# SparkFun_MicroMod_ESP32_27012021.net
KiCad netlist of a schematic drawn in EAGLE
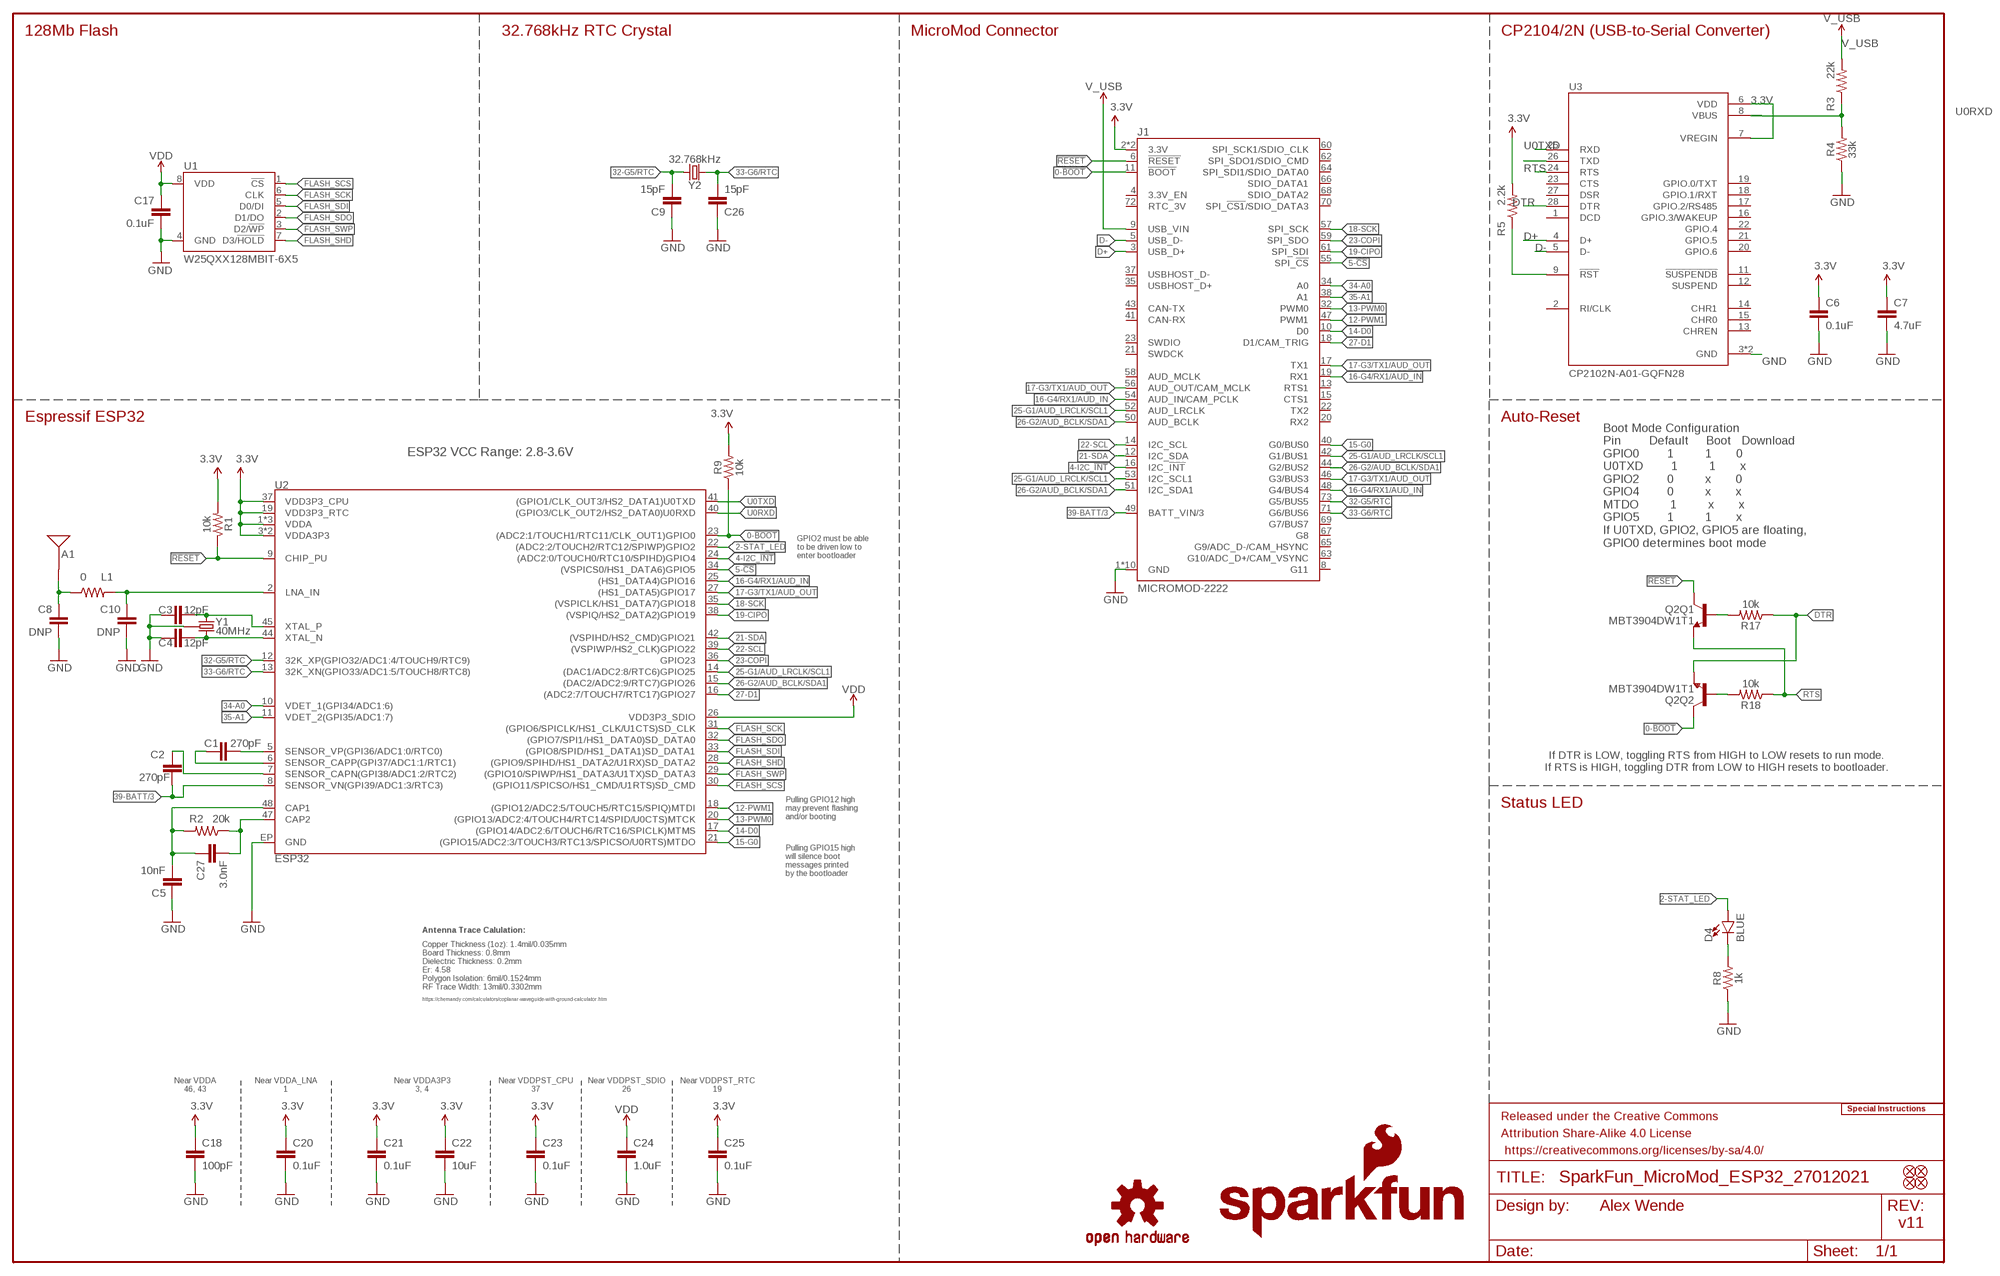
[diagram p0: schematic, sheet 1]

(export (version "E")
  (design (tool "Eeschema 10.0.6"))
  (components
    (comp (ref "A1")
      (value "ANTENNA2.4GHZ-8.0X1.0MM")
      (footprint "eagle-import:ANT-2.4GHZ-8.0X1.0MM")
      (libsource (lib "eagle-import") (part "ANTENNA2.4GHZ-8.0X1.0MM"))
    )
    (comp (ref "C1")
      (value "270pF")
      (footprint "eagle-import:0402-TIGHT")
      (libsource (lib "eagle-import") (part "270PF-0402T-50V-5%"))
    )
    (comp (ref "C2")
      (value "270pF")
      (footprint "eagle-import:0402-TIGHT")
      (libsource (lib "eagle-import") (part "270PF-0402T-50V-5%"))
    )
    (comp (ref "C3")
      (value "12pF")
      (footprint "eagle-import:0402-TIGHT")
      (libsource (lib "eagle-import") (part "12PF-0402T-50V-5%"))
    )
    (comp (ref "C4")
      (value "12pF")
      (footprint "eagle-import:0402-TIGHT")
      (libsource (lib "eagle-import") (part "12PF-0402T-50V-5%"))
    )
    (comp (ref "C5")
      (value "10nF")
      (footprint "eagle-import:0402-TIGHT")
      (libsource (lib "eagle-import") (part "10NF-0402T-25V-10%"))
    )
    (comp (ref "C6")
      (value "0.1uF")
      (footprint "eagle-import:0402-TIGHT")
      (libsource (lib "eagle-import") (part "0.1UF-0402T-16V-10%"))
    )
    (comp (ref "C7")
      (value "4.7uF")
      (footprint "eagle-import:0402-TIGHT")
      (libsource (lib "eagle-import") (part "4.7UF-0402_TIGHT-6.3V-20%-X5R"))
    )
    (comp (ref "C8")
      (value "DNP")
      (footprint "eagle-import:0402-TIGHT")
      (libsource (lib "eagle-import") (part "CAP-0402-TIGHT"))
    )
    (comp (ref "C9")
      (value "15pF")
      (footprint "eagle-import:0402-TIGHT")
      (libsource (lib "eagle-import") (part "15PF-0402T-50V-5%"))
    )
    (comp (ref "C10")
      (value "DNP")
      (footprint "eagle-import:0402-TIGHT")
      (libsource (lib "eagle-import") (part "CAP-0402-TIGHT"))
    )
    (comp (ref "C17")
      (value "0.1uF")
      (footprint "eagle-import:0402-TIGHT")
      (libsource (lib "eagle-import") (part "0.1UF-0402T-16V-10%"))
    )
    (comp (ref "C18")
      (value "100pF")
      (footprint "eagle-import:0402-TIGHT")
      (libsource (lib "eagle-import") (part "100PF-0402T-50V-5%"))
    )
    (comp (ref "C20")
      (value "0.1uF")
      (footprint "eagle-import:0402-TIGHT")
      (libsource (lib "eagle-import") (part "0.1UF-0402T-16V-10%"))
    )
    (comp (ref "C21")
      (value "0.1uF")
      (footprint "eagle-import:0402-TIGHT")
      (libsource (lib "eagle-import") (part "0.1UF-0402T-16V-10%"))
    )
    (comp (ref "C22")
      (value "10uF")
      (footprint "eagle-import:0402-TIGHT")
      (libsource (lib "eagle-import") (part "10UF-0402T-6.3V-20%"))
    )
    (comp (ref "C23")
      (value "0.1uF")
      (footprint "eagle-import:0402-TIGHT")
      (libsource (lib "eagle-import") (part "0.1UF-0402T-16V-10%"))
    )
    (comp (ref "C24")
      (value "1.0uF")
      (footprint "eagle-import:0402-TIGHT")
      (libsource (lib "eagle-import") (part "1.0UF-0402T-16V-10%"))
    )
    (comp (ref "C25")
      (value "0.1uF")
      (footprint "eagle-import:0402-TIGHT")
      (libsource (lib "eagle-import") (part "0.1UF-0402T-16V-10%"))
    )
    (comp (ref "C26")
      (value "15pF")
      (footprint "eagle-import:0402-TIGHT")
      (libsource (lib "eagle-import") (part "15PF-0402T-50V-5%"))
    )
    (comp (ref "C27")
      (value "3.0nF")
      (footprint "eagle-import:0402-TIGHT")
      (libsource (lib "eagle-import") (part "3.0NF-0402T-50V-5%"))
    )
    (comp (ref "D4")
      (value "BLUE")
      (footprint "eagle-import:LED-0603")
      (libsource (lib "eagle-import") (part "LED-BLUE0603"))
    )
    (comp (ref "FD1")
      (value "FIDUCIALUFIDUCIAL")
      (footprint "eagle-import:FIDUCIAL-MICRO")
      (libsource (lib "eagle-import") (part "FIDUCIALUFIDUCIAL"))
    )
    (comp (ref "FD2")
      (value "FIDUCIALUFIDUCIAL")
      (footprint "eagle-import:FIDUCIAL-MICRO")
      (libsource (lib "eagle-import") (part "FIDUCIALUFIDUCIAL"))
    )
    (comp (ref "FD3")
      (value "FIDUCIALUFIDUCIAL")
      (footprint "eagle-import:FIDUCIAL-MICRO")
      (libsource (lib "eagle-import") (part "FIDUCIALUFIDUCIAL"))
    )
    (comp (ref "FD4")
      (value "FIDUCIALUFIDUCIAL")
      (footprint "eagle-import:FIDUCIAL-MICRO")
      (libsource (lib "eagle-import") (part "FIDUCIALUFIDUCIAL"))
    )
    (comp (ref "FRAME1")
      (value "FRAME-LEDGER")
      (footprint "eagle-import:CREATIVE_COMMONS")
      (libsource (lib "eagle-import") (part "FRAME-LEDGER"))
    )
    (comp (ref "J1")
      (value "MICROMOD-2222")
      (footprint "eagle-import:M.2-CARD-E-22")
      (libsource (lib "eagle-import") (part "MICROMOD-2222"))
    )
    (comp (ref "L1")
      (value "0")
      (footprint "eagle-import:0402-TIGHT")
      (libsource (lib "eagle-import") (part "0OHM-0402T-1/10W"))
    )
    (comp (ref "LOGO1")
      (value "SPECIAL_INSTRUCTIONS-ORDERING")
      (footprint "eagle-import:ORDERING_INSTRUCTIONS")
      (libsource (lib "eagle-import") (part "SPECIAL_INSTRUCTIONS-ORDERING"))
    )
    (comp (ref "LOGO2")
      (value "SFE_LOGO_NAME_FLAME.1_INCH")
      (footprint "eagle-import:SFE_LOGO_NAME_FLAME_.1")
      (libsource (lib "eagle-import") (part "SFE_LOGO_NAME_FLAME.1_INCH"))
    )
    (comp (ref "LOGO3")
      (value "OSHW-LOGOS")
      (footprint "eagle-import:OSHW-LOGO-S")
      (libsource (lib "eagle-import") (part "OSHW-LOGOS"))
    )
    (comp (ref "Q2")
      (value "MBT3904DW1T1")
      (footprint "eagle-import:SC70-6")
      (libsource (lib "eagle-import") (part "TRANS_NPN_DUAL-MBT3904DW1T1"))
    )
    (comp (ref "R1")
      (value "10k")
      (footprint "eagle-import:0402-TIGHT")
      (libsource (lib "eagle-import") (part "10KOHM-0402T-1/16W-1%"))
    )
    (comp (ref "R2")
      (value "20k")
      (footprint "eagle-import:0402-TIGHT")
      (libsource (lib "eagle-import") (part "20KOHM-0402T-1/16W-1%"))
    )
    (comp (ref "R3")
      (value "22k")
      (footprint "eagle-import:0402-TIGHT")
      (libsource (lib "eagle-import") (part "22KOHM-0402_TIGHT-1/10W-1%"))
    )
    (comp (ref "R4")
      (value "33k")
      (footprint "eagle-import:0402-TIGHT")
      (libsource (lib "eagle-import") (part "33KOHM-0402T-1/16W-1%"))
    )
    (comp (ref "R5")
      (value "2.2k")
      (footprint "eagle-import:0402-TIGHT")
      (libsource (lib "eagle-import") (part "2.2KOHM-0402T-1/16W-1%"))
    )
    (comp (ref "R8")
      (value "1k")
      (footprint "eagle-import:0402-TIGHT")
      (libsource (lib "eagle-import") (part "1KOHM-0402T-1/16W-1%"))
    )
    (comp (ref "R9")
      (value "10k")
      (footprint "eagle-import:0402-TIGHT")
      (libsource (lib "eagle-import") (part "10KOHM-0402T-1/16W-1%"))
    )
    (comp (ref "R17")
      (value "10k")
      (footprint "eagle-import:0402-TIGHT")
      (libsource (lib "eagle-import") (part "10KOHM-0402T-1/16W-1%"))
    )
    (comp (ref "R18")
      (value "10k")
      (footprint "eagle-import:0402-TIGHT")
      (libsource (lib "eagle-import") (part "10KOHM-0402T-1/16W-1%"))
    )
    (comp (ref "U1")
      (value "W25QXX128MBIT-6X5")
      (footprint "eagle-import:WSON-8-6X5")
      (libsource (lib "eagle-import") (part "W25QXX128MBIT-6X5"))
    )
    (comp (ref "U2")
      (value "ESP32")
      (footprint "eagle-import:QFN48-0.4MM")
      (libsource (lib "eagle-import") (part "ESP32"))
    )
    (comp (ref "U3")
      (value "CP2102N-A01-GQFN28")
      (footprint "eagle-import:QFN50P500X500X80-29N")
      (fields (field (name "MF") "Silicon Labs"))
      (libsource (lib "eagle-import") (part "CP2102N-A01-GQFN28"))
    )
    (comp (ref "Y1")
      (value "40MHz")
      (footprint "eagle-import:CRYSTAL-SMD-2X2.5MM")
      (libsource (lib "eagle-import") (part "CRYSTAL-40MHZ-SMD-2X2.5MM"))
    )
    (comp (ref "Y2")
      (value "32.768kHz")
      (footprint "eagle-import:CRYSTAL-SMD-3.2X1.5MM")
      (libsource (lib "eagle-import") (part "CRYSTAL-32.768KHZSMD-3.2X1.5"))
    )
  )
  (nets
    (net (code "1") (name "/0-~{BOOT}") (class "Default")
      (node (ref "J1") (pin "11") (pinfunction "~{BOOT}_11") (pintype "bidirectional"))
      (node (ref "Q2") (pin "6") (pinfunction "C_6") (pintype "passive"))
      (node (ref "R9") (pin "1") (pinfunction "1_1") (pintype "passive"))
      (node (ref "U2") (pin "23") (pinfunction "(ADC2:1/TOUCH1/RTC11/CLK_OUT1)GPIO0_23") (pintype "bidirectional"))
    )
    (net (code "2") (name "/4-I2C_~{INT}") (class "Default")
      (node (ref "J1") (pin "16") (pinfunction "I2C_~{INT}_16") (pintype "bidirectional"))
      (node (ref "U2") (pin "24") (pinfunction "(ADC2:0/TOUCH0/RTC10/SPIHD)GPIO4_24") (pintype "bidirectional"))
    )
    (net (code "3") (name "/5-~{CS}") (class "Default")
      (node (ref "J1") (pin "55") (pinfunction "SPI_~{CS}_55") (pintype "bidirectional"))
      (node (ref "U2") (pin "34") (pinfunction "(VSPICS0/HS1_DATA6)GPIO5_34") (pintype "bidirectional"))
    )
    (net (code "4") (name "/~{RESET}") (class "Default")
      (node (ref "J1") (pin "6") (pinfunction "~{RESET}_6") (pintype "bidirectional"))
      (node (ref "Q2") (pin "3") (pinfunction "C_3") (pintype "passive"))
      (node (ref "R1") (pin "1") (pinfunction "1_1") (pintype "passive"))
      (node (ref "U2") (pin "9") (pinfunction "CHIP_PU_9") (pintype "bidirectional"))
    )
    (net (code "5") (name "2-STAT_LED") (class "Default")
      (node (ref "D4") (pin "A") (pinfunction "A_A") (pintype "passive"))
      (node (ref "U2") (pin "22") (pinfunction "(ADC2:2/TOUCH2/RTC12/SPIWP)GPIO2_22") (pintype "bidirectional"))
    )
    (net (code "6") (name "3.3V") (class "Default")
      (node (ref "C18") (pin "1") (pinfunction "1_1") (pintype "passive"))
      (node (ref "C20") (pin "1") (pinfunction "1_1") (pintype "passive"))
      (node (ref "C21") (pin "1") (pinfunction "1_1") (pintype "passive"))
      (node (ref "C22") (pin "1") (pinfunction "1_1") (pintype "passive"))
      (node (ref "C23") (pin "1") (pinfunction "1_1") (pintype "passive"))
      (node (ref "C25") (pin "1") (pinfunction "1_1") (pintype "passive"))
      (node (ref "C6") (pin "1") (pinfunction "1_1") (pintype "passive"))
      (node (ref "C7") (pin "1") (pinfunction "1_1") (pintype "passive"))
      (node (ref "J1") (pin "2") (pinfunction "3.3V_2") (pintype "bidirectional"))
      (node (ref "J1") (pin "74") (pinfunction "3.3V_74") (pintype "bidirectional"))
      (node (ref "R1") (pin "2") (pinfunction "2_2") (pintype "passive"))
      (node (ref "R5") (pin "2") (pinfunction "2_2") (pintype "passive"))
      (node (ref "R9") (pin "2") (pinfunction "2_2") (pintype "passive"))
      (node (ref "U2") (pin "1") (pinfunction "VDDA_1") (pintype "bidirectional"))
      (node (ref "U2") (pin "19") (pinfunction "VDD3P3_RTC_19") (pintype "bidirectional"))
      (node (ref "U2") (pin "3") (pinfunction "VDDA3P3_3") (pintype "bidirectional"))
      (node (ref "U2") (pin "37") (pinfunction "VDD3P3_CPU_37") (pintype "bidirectional"))
      (node (ref "U2") (pin "4") (pinfunction "VDDA3P3_4") (pintype "bidirectional"))
      (node (ref "U2") (pin "43") (pinfunction "VDDA_43") (pintype "bidirectional"))
      (node (ref "U2") (pin "46") (pinfunction "VDDA_46") (pintype "bidirectional"))
      (node (ref "U3") (pin "6") (pinfunction "VDD_6") (pintype "power_in"))
      (node (ref "U3") (pin "7") (pinfunction "VREGIN_7") (pintype "power_in"))
    )
    (net (code "7") (name "12-PWM1") (class "Default")
      (node (ref "J1") (pin "47") (pinfunction "PWM1_47") (pintype "bidirectional"))
      (node (ref "U2") (pin "18") (pinfunction "(GPIO12/ADC2:5/TOUCH5/RTC15/SPIQ)MTDI_18") (pintype "bidirectional"))
    )
    (net (code "8") (name "13-PWM0") (class "Default")
      (node (ref "J1") (pin "32") (pinfunction "PWM0_32") (pintype "bidirectional"))
      (node (ref "U2") (pin "20") (pinfunction "(GPIO13/ADC2:4/TOUCH4/RTC14/SPID/U0CTS)MTCK_20") (pintype "bidirectional"))
    )
    (net (code "9") (name "14-D0") (class "Default")
      (node (ref "J1") (pin "10") (pinfunction "D0_10") (pintype "bidirectional"))
      (node (ref "U2") (pin "17") (pinfunction "(GPIO14/ADC2:6/TOUCH6/RTC16/SPICLK)MTMS_17") (pintype "bidirectional"))
    )
    (net (code "10") (name "15-G0") (class "Default")
      (node (ref "J1") (pin "40") (pinfunction "G0/BUS0_40") (pintype "bidirectional"))
      (node (ref "U2") (pin "21") (pinfunction "(GPIO15/ADC2:3/TOUCH3/RTC13/SPICSO/U0RTS)MTDO_21") (pintype "bidirectional"))
    )
    (net (code "11") (name "16-G4{slash}RX1{slash}AUD_IN") (class "Default")
      (node (ref "J1") (pin "19") (pinfunction "RX1_19") (pintype "bidirectional"))
      (node (ref "J1") (pin "48") (pinfunction "G4/BUS4_48") (pintype "bidirectional"))
      (node (ref "J1") (pin "54") (pinfunction "AUD_IN/CAM_PCLK_54") (pintype "bidirectional"))
      (node (ref "U2") (pin "25") (pinfunction "(HS1_DATA4)GPIO16_25") (pintype "bidirectional"))
    )
    (net (code "12") (name "17-G3{slash}TX1{slash}AUD_OUT") (class "Default")
      (node (ref "J1") (pin "17") (pinfunction "TX1_17") (pintype "bidirectional"))
      (node (ref "J1") (pin "46") (pinfunction "G3/BUS3_46") (pintype "bidirectional"))
      (node (ref "J1") (pin "56") (pinfunction "AUD_OUT/CAM_MCLK_56") (pintype "bidirectional"))
      (node (ref "U2") (pin "27") (pinfunction "(HS1_DATA5)GPIO17_27") (pintype "bidirectional"))
    )
    (net (code "13") (name "18-SCK") (class "Default")
      (node (ref "J1") (pin "57") (pinfunction "SPI_SCK_57") (pintype "bidirectional"))
      (node (ref "U2") (pin "35") (pinfunction "(VSPICLK/HS1_DATA7)GPIO18_35") (pintype "bidirectional"))
    )
    (net (code "14") (name "19-CIPO") (class "Default")
      (node (ref "J1") (pin "61") (pinfunction "SPI_SDI_61") (pintype "bidirectional"))
      (node (ref "U2") (pin "38") (pinfunction "(VSPIQ/HS2_DATA2)GPIO19_38") (pintype "bidirectional"))
    )
    (net (code "15") (name "21-SDA") (class "Default")
      (node (ref "J1") (pin "12") (pinfunction "I2C_SDA_12") (pintype "bidirectional"))
      (node (ref "U2") (pin "42") (pinfunction "(VSPIHD/HS2_CMD)GPIO21_42") (pintype "bidirectional"))
    )
    (net (code "16") (name "22-SCL") (class "Default")
      (node (ref "J1") (pin "14") (pinfunction "I2C_SCL_14") (pintype "bidirectional"))
      (node (ref "U2") (pin "39") (pinfunction "(VSPIWP/HS2_CLK)GPIO22_39") (pintype "bidirectional"))
    )
    (net (code "17") (name "23-COPI") (class "Default")
      (node (ref "J1") (pin "59") (pinfunction "SPI_SDO_59") (pintype "bidirectional"))
      (node (ref "U2") (pin "36") (pinfunction "GPIO23_36") (pintype "bidirectional"))
    )
    (net (code "18") (name "25-G1{slash}AUD_LRCLK{slash}SCL1") (class "Default")
      (node (ref "J1") (pin "42") (pinfunction "G1/BUS1_42") (pintype "bidirectional"))
      (node (ref "J1") (pin "52") (pinfunction "AUD_LRCLK_52") (pintype "bidirectional"))
      (node (ref "J1") (pin "53") (pinfunction "I2C_SCL1_53") (pintype "bidirectional"))
      (node (ref "U2") (pin "14") (pinfunction "(DAC1/ADC2:8/RTC6)GPIO25_14") (pintype "bidirectional"))
    )
    (net (code "19") (name "26-G2{slash}AUD_BCLK{slash}SDA1") (class "Default")
      (node (ref "J1") (pin "44") (pinfunction "G2/BUS2_44") (pintype "bidirectional"))
      (node (ref "J1") (pin "50") (pinfunction "AUD_BCLK_50") (pintype "bidirectional"))
      (node (ref "J1") (pin "51") (pinfunction "I2C_SDA1_51") (pintype "bidirectional"))
      (node (ref "U2") (pin "15") (pinfunction "(DAC2/ADC2:9/RTC7)GPIO26_15") (pintype "bidirectional"))
    )
    (net (code "20") (name "27-D1") (class "Default")
      (node (ref "J1") (pin "18") (pinfunction "D1/CAM_TRIG_18") (pintype "bidirectional"))
      (node (ref "U2") (pin "16") (pinfunction "(ADC2:7/TOUCH7/RTC17)GPIO27_16") (pintype "bidirectional"))
    )
    (net (code "21") (name "32-G5{slash}RTC") (class "Default")
      (node (ref "C9") (pin "2") (pinfunction "2_2") (pintype "passive"))
      (node (ref "J1") (pin "73") (pinfunction "G5/BUS5_73") (pintype "bidirectional"))
      (node (ref "U2") (pin "12") (pinfunction "32K_XP(GPIO32/ADC1:4/TOUCH9/RTC9)_12") (pintype "bidirectional"))
      (node (ref "Y2") (pin "P$1") (pinfunction "1_P$1") (pintype "passive"))
    )
    (net (code "22") (name "33-G6{slash}RTC") (class "Default")
      (node (ref "C26") (pin "2") (pinfunction "2_2") (pintype "passive"))
      (node (ref "J1") (pin "71") (pinfunction "G6/BUS6_71") (pintype "bidirectional"))
      (node (ref "U2") (pin "13") (pinfunction "32K_XN(GPIO33/ADC1:5/TOUCH8/RTC8)_13") (pintype "bidirectional"))
      (node (ref "Y2") (pin "P$2") (pinfunction "2_P$2") (pintype "passive"))
    )
    (net (code "23") (name "34-A0") (class "Default")
      (node (ref "J1") (pin "34") (pinfunction "A0_34") (pintype "bidirectional"))
      (node (ref "U2") (pin "10") (pinfunction "VDET_1(GPI34/ADC1:6)_10") (pintype "bidirectional"))
    )
    (net (code "24") (name "35-A1") (class "Default")
      (node (ref "J1") (pin "38") (pinfunction "A1_38") (pintype "bidirectional"))
      (node (ref "U2") (pin "11") (pinfunction "VDET_2(GPI35/ADC1:7)_11") (pintype "bidirectional"))
    )
    (net (code "25") (name "39-BATT{slash}3") (class "Default")
      (node (ref "C2") (pin "2") (pinfunction "2_2") (pintype "passive"))
      (node (ref "J1") (pin "49") (pinfunction "BATT_VIN/3_49") (pintype "bidirectional"))
      (node (ref "U2") (pin "8") (pinfunction "SENSOR_VN(GPI39/ADC1:3/RTC3)_8") (pintype "bidirectional"))
    )
    (net (code "26") (name "D+") (class "Default")
      (node (ref "J1") (pin "3") (pinfunction "USB_D+_3") (pintype "bidirectional"))
      (node (ref "U3") (pin "4") (pinfunction "D+_4") (pintype "bidirectional"))
    )
    (net (code "27") (name "D-") (class "Default")
      (node (ref "J1") (pin "5") (pinfunction "USB_D-_5") (pintype "bidirectional"))
      (node (ref "U3") (pin "5") (pinfunction "D-_5") (pintype "bidirectional"))
    )
    (net (code "28") (name "DTR") (class "Default")
      (node (ref "Q2") (pin "1") (pinfunction "E_1") (pintype "passive"))
      (node (ref "R17") (pin "1") (pinfunction "1_1") (pintype "passive"))
      (node (ref "U3") (pin "28") (pinfunction "DTR_28") (pintype "output"))
    )
    (net (code "29") (name "FLASH_SCK") (class "Default")
      (node (ref "U1") (pin "6") (pinfunction "CLK_6") (pintype "bidirectional"))
      (node (ref "U2") (pin "31") (pinfunction "(GPIO6/SPICLK/HS1_CLK/U1CTS)SD_CLK_31") (pintype "bidirectional"))
    )
    (net (code "30") (name "FLASH_SCS") (class "Default")
      (node (ref "U1") (pin "1") (pinfunction "~{CS}_1") (pintype "bidirectional"))
      (node (ref "U2") (pin "30") (pinfunction "(GPIO11/SPICSO/HS1_CMD/U1RTS)SD_CMD_30") (pintype "bidirectional"))
    )
    (net (code "31") (name "FLASH_SDI") (class "Default")
      (node (ref "U1") (pin "5") (pinfunction "D0/DI_5") (pintype "bidirectional"))
      (node (ref "U2") (pin "33") (pinfunction "(GPIO8/SPID/HS1_DATA1)SD_DATA1_33") (pintype "bidirectional"))
    )
    (net (code "32") (name "FLASH_SDO") (class "Default")
      (node (ref "U1") (pin "2") (pinfunction "D1/DO_2") (pintype "bidirectional"))
      (node (ref "U2") (pin "32") (pinfunction "(GPIO7/SPI1/HS1_DATA0)SD_DATA0_32") (pintype "bidirectional"))
    )
    (net (code "33") (name "FLASH_SHD") (class "Default")
      (node (ref "U1") (pin "7") (pinfunction "D3/~{HOLD}_7") (pintype "bidirectional"))
      (node (ref "U2") (pin "28") (pinfunction "(GPIO9/SPIHD/HS1_DATA2/U1RX)SD_DATA2_28") (pintype "bidirectional"))
    )
    (net (code "34") (name "FLASH_SWP") (class "Default")
      (node (ref "U1") (pin "3") (pinfunction "D2/~{WP}_3") (pintype "bidirectional"))
      (node (ref "U2") (pin "29") (pinfunction "(GPIO10/SPIWP/HS1_DATA3/U1TX)SD_DATA3_29") (pintype "bidirectional"))
    )
    (net (code "35") (name "GND") (class "Default")
      (node (ref "C10") (pin "2") (pinfunction "2_2") (pintype "passive"))
      (node (ref "C17") (pin "2") (pinfunction "2_2") (pintype "passive"))
      (node (ref "C18") (pin "2") (pinfunction "2_2") (pintype "passive"))
      (node (ref "C20") (pin "2") (pinfunction "2_2") (pintype "passive"))
      (node (ref "C21") (pin "2") (pinfunction "2_2") (pintype "passive"))
      (node (ref "C22") (pin "2") (pinfunction "2_2") (pintype "passive"))
      (node (ref "C23") (pin "2") (pinfunction "2_2") (pintype "passive"))
      (node (ref "C24") (pin "2") (pinfunction "2_2") (pintype "passive"))
      (node (ref "C25") (pin "2") (pinfunction "2_2") (pintype "passive"))
      (node (ref "C26") (pin "1") (pinfunction "1_1") (pintype "passive"))
      (node (ref "C3") (pin "1") (pinfunction "1_1") (pintype "passive"))
      (node (ref "C4") (pin "1") (pinfunction "1_1") (pintype "passive"))
      (node (ref "C5") (pin "1") (pinfunction "1_1") (pintype "passive"))
      (node (ref "C6") (pin "2") (pinfunction "2_2") (pintype "passive"))
      (node (ref "C7") (pin "2") (pinfunction "2_2") (pintype "passive"))
      (node (ref "C8") (pin "2") (pinfunction "2_2") (pintype "passive"))
      (node (ref "C9") (pin "1") (pinfunction "1_1") (pintype "passive"))
      (node (ref "J1") (pin "1") (pinfunction "GND_1") (pintype "bidirectional"))
      (node (ref "J1") (pin "33") (pinfunction "GND_33") (pintype "bidirectional"))
      (node (ref "J1") (pin "36") (pinfunction "GND_36") (pintype "bidirectional"))
      (node (ref "J1") (pin "39") (pinfunction "GND_39") (pintype "bidirectional"))
      (node (ref "J1") (pin "45") (pinfunction "GND_45") (pintype "bidirectional"))
      (node (ref "J1") (pin "7") (pinfunction "GND_7") (pintype "bidirectional"))
      (node (ref "J1") (pin "75") (pinfunction "GND_75") (pintype "bidirectional"))
      (node (ref "J1") (pin "GND1") (pinfunction "GND_GND1") (pintype "bidirectional"))
      (node (ref "J1") (pin "GND2") (pinfunction "GND_GND2") (pintype "bidirectional"))
      (node (ref "J1") (pin "GND3") (pinfunction "GND_GND3") (pintype "bidirectional"))
      (node (ref "R4") (pin "1") (pinfunction "1_1") (pintype "passive"))
      (node (ref "R8") (pin "1") (pinfunction "1_1") (pintype "passive"))
      (node (ref "U1") (pin "4") (pinfunction "GND_4") (pintype "bidirectional"))
      (node (ref "U2") (pin "EP") (pinfunction "GND_EP") (pintype "bidirectional"))
      (node (ref "U3") (pin "29") (pinfunction "GND_29") (pintype "power_in"))
      (node (ref "U3") (pin "3") (pinfunction "GND_3") (pintype "power_in"))
      (node (ref "Y1") (pin "P2") (pinfunction "GND_P2") (pintype "power_in"))
      (node (ref "Y1") (pin "P4") (pinfunction "GND_P4") (pintype "power_in"))
    )
    (net (code "36") (name "Net-(A1-SIGNAL)") (class "Default")
      (node (ref "A1") (pin "FEED") (pinfunction "SIGNAL_FEED") (pintype "bidirectional"))
      (node (ref "C8") (pin "1") (pinfunction "1_1") (pintype "passive"))
      (node (ref "L1") (pin "1") (pinfunction "1_1") (pintype "passive"))
    )
    (net (code "37") (name "Net-(D4-PadC)") (class "Default")
      (node (ref "D4") (pin "C") (pinfunction "C_C") (pintype "passive"))
      (node (ref "R8") (pin "2") (pinfunction "2_2") (pintype "passive"))
    )
    (net (code "38") (name "Net-(Q2A-B)") (class "Default")
      (node (ref "Q2") (pin "5") (pinfunction "B_5") (pintype "passive"))
      (node (ref "R17") (pin "2") (pinfunction "2_2") (pintype "passive"))
    )
    (net (code "39") (name "Net-(Q2B-B)") (class "Default")
      (node (ref "Q2") (pin "2") (pinfunction "B_2") (pintype "passive"))
      (node (ref "R18") (pin "2") (pinfunction "2_2") (pintype "passive"))
    )
    (net (code "40") (name "Net-(U2-CAP1)") (class "Default")
      (node (ref "C27") (pin "1") (pinfunction "1_1") (pintype "passive"))
      (node (ref "C5") (pin "2") (pinfunction "2_2") (pintype "passive"))
      (node (ref "R2") (pin "2") (pinfunction "2_2") (pintype "passive"))
      (node (ref "U2") (pin "48") (pinfunction "CAP1_48") (pintype "bidirectional"))
    )
    (net (code "41") (name "Net-(U2-CAP2)") (class "Default")
      (node (ref "C27") (pin "2") (pinfunction "2_2") (pintype "passive"))
      (node (ref "R2") (pin "1") (pinfunction "1_1") (pintype "passive"))
      (node (ref "U2") (pin "47") (pinfunction "CAP2_47") (pintype "bidirectional"))
    )
    (net (code "42") (name "Net-(U2-LNA_IN)") (class "Default")
      (node (ref "C10") (pin "1") (pinfunction "1_1") (pintype "passive"))
      (node (ref "L1") (pin "2") (pinfunction "2_2") (pintype "passive"))
      (node (ref "U2") (pin "2") (pinfunction "LNA_IN_2") (pintype "bidirectional"))
    )
    (net (code "43") (name "Net-(U2-SENSOR_CAPN(GPI38{slash}ADC1:2{slash}RTC2))") (class "Default")
      (node (ref "C2") (pin "1") (pinfunction "1_1") (pintype "passive"))
      (node (ref "U2") (pin "7") (pinfunction "SENSOR_CAPN(GPI38/ADC1:2/RTC2)_7") (pintype "bidirectional"))
    )
    (net (code "44") (name "Net-(U2-SENSOR_CAPP(GPI37{slash}ADC1:1{slash}RTC1))") (class "Default")
      (node (ref "C1") (pin "1") (pinfunction "1_1") (pintype "passive"))
      (node (ref "U2") (pin "6") (pinfunction "SENSOR_CAPP(GPI37/ADC1:1/RTC1)_6") (pintype "bidirectional"))
    )
    (net (code "45") (name "Net-(U2-SENSOR_VP(GPI36{slash}ADC1:0{slash}RTC0))") (class "Default")
      (node (ref "C1") (pin "2") (pinfunction "2_2") (pintype "passive"))
      (node (ref "U2") (pin "5") (pinfunction "SENSOR_VP(GPI36/ADC1:0/RTC0)_5") (pintype "bidirectional"))
    )
    (net (code "46") (name "Net-(U2-XTAL_N)") (class "Default")
      (node (ref "C4") (pin "2") (pinfunction "2_2") (pintype "passive"))
      (node (ref "U2") (pin "44") (pinfunction "XTAL_N_44") (pintype "bidirectional"))
      (node (ref "Y1") (pin "P3") (pinfunction "2_P3") (pintype "passive"))
    )
    (net (code "47") (name "Net-(U2-XTAL_P)") (class "Default")
      (node (ref "C3") (pin "2") (pinfunction "2_2") (pintype "passive"))
      (node (ref "U2") (pin "45") (pinfunction "XTAL_P_45") (pintype "bidirectional"))
      (node (ref "Y1") (pin "P1") (pinfunction "1_P1") (pintype "passive"))
    )
    (net (code "48") (name "Net-(U3-VBUS)") (class "Default")
      (node (ref "R3") (pin "1") (pinfunction "1_1") (pintype "passive"))
      (node (ref "R4") (pin "2") (pinfunction "2_2") (pintype "passive"))
      (node (ref "U3") (pin "8") (pinfunction "VBUS_8") (pintype "power_in"))
    )
    (net (code "49") (name "Net-(U3-~{RST})") (class "Default")
      (node (ref "R5") (pin "1") (pinfunction "1_1") (pintype "passive"))
      (node (ref "U3") (pin "9") (pinfunction "~{RST}_9") (pintype "input"))
    )
    (net (code "50") (name "RTS") (class "Default")
      (node (ref "Q2") (pin "4") (pinfunction "E_4") (pintype "passive"))
      (node (ref "R18") (pin "1") (pinfunction "1_1") (pintype "passive"))
      (node (ref "U3") (pin "24") (pinfunction "RTS_24") (pintype "output"))
    )
    (net (code "51") (name "U0RXD") (class "Default")
      (node (ref "U2") (pin "40") (pinfunction "(GPIO3/CLK_OUT2/HS2_DATA0)U0RXD_40") (pintype "bidirectional"))
      (node (ref "U3") (pin "26") (pinfunction "TXD_26") (pintype "output"))
    )
    (net (code "52") (name "U0TXD") (class "Default")
      (node (ref "U2") (pin "41") (pinfunction "(GPIO1/CLK_OUT3/HS2_DATA1)U0TXD_41") (pintype "bidirectional"))
      (node (ref "U3") (pin "25") (pinfunction "RXD_25") (pintype "input"))
    )
    (net (code "53") (name "VDD") (class "Default")
      (node (ref "C17") (pin "1") (pinfunction "1_1") (pintype "passive"))
      (node (ref "C24") (pin "1") (pinfunction "1_1") (pintype "passive"))
      (node (ref "U1") (pin "8") (pinfunction "VDD_8") (pintype "bidirectional"))
      (node (ref "U2") (pin "26") (pinfunction "VDD3P3_SDIO_26") (pintype "bidirectional"))
    )
    (net (code "54") (name "V_USB") (class "Default")
      (node (ref "J1") (pin "9") (pinfunction "USB_VIN_9") (pintype "bidirectional"))
      (node (ref "R3") (pin "2") (pinfunction "2_2") (pintype "passive"))
    )
    (net (code "55") (name "unconnected-(J1-3.3V_EN-Pad4)") (class "Default")
      (node (ref "J1") (pin "4") (pinfunction "3.3V_EN_4") (pintype "bidirectional"))
    )
    (net (code "56") (name "unconnected-(J1-AUD_MCLK-Pad58)") (class "Default")
      (node (ref "J1") (pin "58") (pinfunction "AUD_MCLK_58") (pintype "bidirectional"))
    )
    (net (code "57") (name "unconnected-(J1-CAN-RX-Pad41)") (class "Default")
      (node (ref "J1") (pin "41") (pinfunction "CAN-RX_41") (pintype "bidirectional"))
    )
    (net (code "58") (name "unconnected-(J1-CAN-TX-Pad43)") (class "Default")
      (node (ref "J1") (pin "43") (pinfunction "CAN-TX_43") (pintype "bidirectional"))
    )
    (net (code "59") (name "unconnected-(J1-CTS1-Pad15)") (class "Default")
      (node (ref "J1") (pin "15") (pinfunction "CTS1_15") (pintype "bidirectional"))
    )
    (net (code "60") (name "unconnected-(J1-G7{slash}BUS7-Pad69)") (class "Default")
      (node (ref "J1") (pin "69") (pinfunction "G7/BUS7_69") (pintype "bidirectional"))
    )
    (net (code "61") (name "unconnected-(J1-G8-Pad67)") (class "Default")
      (node (ref "J1") (pin "67") (pinfunction "G8_67") (pintype "bidirectional"))
    )
    (net (code "62") (name "unconnected-(J1-G9{slash}ADC_D-{slash}CAM_HSYNC-Pad65)") (class "Default")
      (node (ref "J1") (pin "65") (pinfunction "G9/ADC_D-/CAM_HSYNC_65") (pintype "bidirectional"))
    )
    (net (code "63") (name "unconnected-(J1-G10{slash}ADC_D+{slash}CAM_VSYNC-Pad63)") (class "Default")
      (node (ref "J1") (pin "63") (pinfunction "G10/ADC_D+/CAM_VSYNC_63") (pintype "bidirectional"))
    )
    (net (code "64") (name "unconnected-(J1-G11-Pad8)") (class "Default")
      (node (ref "J1") (pin "8") (pinfunction "G11_8") (pintype "bidirectional"))
    )
    (net (code "65") (name "unconnected-(J1-RTC_3V-Pad72)") (class "Default")
      (node (ref "J1") (pin "72") (pinfunction "RTC_3V_72") (pintype "bidirectional"))
    )
    (net (code "66") (name "unconnected-(J1-RTS1-Pad13)") (class "Default")
      (node (ref "J1") (pin "13") (pinfunction "RTS1_13") (pintype "bidirectional"))
    )
    (net (code "67") (name "unconnected-(J1-RX2-Pad20)") (class "Default")
      (node (ref "J1") (pin "20") (pinfunction "RX2_20") (pintype "bidirectional"))
    )
    (net (code "68") (name "unconnected-(J1-SDIO_DATA1-Pad66)") (class "Default")
      (node (ref "J1") (pin "66") (pinfunction "SDIO_DATA1_66") (pintype "bidirectional"))
    )
    (net (code "69") (name "unconnected-(J1-SDIO_DATA2-Pad68)") (class "Default")
      (node (ref "J1") (pin "68") (pinfunction "SDIO_DATA2_68") (pintype "bidirectional"))
    )
    (net (code "70") (name "unconnected-(J1-SPI_SCK1{slash}SDIO_CLK-Pad60)") (class "Default")
      (node (ref "J1") (pin "60") (pinfunction "SPI_SCK1/SDIO_CLK_60") (pintype "bidirectional"))
    )
    (net (code "71") (name "unconnected-(J1-SPI_SDI1{slash}SDIO_DATA0-Pad64)") (class "Default")
      (node (ref "J1") (pin "64") (pinfunction "SPI_SDI1/SDIO_DATA0_64") (pintype "bidirectional"))
    )
    (net (code "72") (name "unconnected-(J1-SPI_SDO1{slash}SDIO_CMD-Pad62)") (class "Default")
      (node (ref "J1") (pin "62") (pinfunction "SPI_SDO1/SDIO_CMD_62") (pintype "bidirectional"))
    )
    (net (code "73") (name "unconnected-(J1-SPI_~{CS1}{slash}SDIO_DATA3-Pad70)") (class "Default")
      (node (ref "J1") (pin "70") (pinfunction "SPI_~{CS1}/SDIO_DATA3_70") (pintype "bidirectional"))
    )
    (net (code "74") (name "unconnected-(J1-SWDCK-Pad21)") (class "Default")
      (node (ref "J1") (pin "21") (pinfunction "SWDCK_21") (pintype "bidirectional"))
    )
    (net (code "75") (name "unconnected-(J1-SWDIO-Pad23)") (class "Default")
      (node (ref "J1") (pin "23") (pinfunction "SWDIO_23") (pintype "bidirectional"))
    )
    (net (code "76") (name "unconnected-(J1-TX2-Pad22)") (class "Default")
      (node (ref "J1") (pin "22") (pinfunction "TX2_22") (pintype "bidirectional"))
    )
    (net (code "77") (name "unconnected-(J1-USBHOST_D+-Pad35)") (class "Default")
      (node (ref "J1") (pin "35") (pinfunction "USBHOST_D+_35") (pintype "bidirectional"))
    )
    (net (code "78") (name "unconnected-(J1-USBHOST_D--Pad37)") (class "Default")
      (node (ref "J1") (pin "37") (pinfunction "USBHOST_D-_37") (pintype "bidirectional"))
    )
    (net (code "79") (name "unconnected-(U3-CHR0-Pad15)") (class "Default")
      (node (ref "U3") (pin "15") (pinfunction "CHR0_15") (pintype "output"))
    )
    (net (code "80") (name "unconnected-(U3-CHR1-Pad14)") (class "Default")
      (node (ref "U3") (pin "14") (pinfunction "CHR1_14") (pintype "output"))
    )
    (net (code "81") (name "unconnected-(U3-CHREN-Pad13)") (class "Default")
      (node (ref "U3") (pin "13") (pinfunction "CHREN_13") (pintype "output"))
    )
    (net (code "82") (name "unconnected-(U3-CTS-Pad23)") (class "Default")
      (node (ref "U3") (pin "23") (pinfunction "CTS_23") (pintype "input"))
    )
    (net (code "83") (name "unconnected-(U3-DCD-Pad1)") (class "Default")
      (node (ref "U3") (pin "1") (pinfunction "DCD_1") (pintype "input"))
    )
    (net (code "84") (name "unconnected-(U3-DSR-Pad27)") (class "Default")
      (node (ref "U3") (pin "27") (pinfunction "DSR_27") (pintype "input"))
    )
    (net (code "85") (name "unconnected-(U3-GPIO.0{slash}TXT-Pad19)") (class "Default")
      (node (ref "U3") (pin "19") (pinfunction "GPIO.0/TXT_19") (pintype "bidirectional"))
    )
    (net (code "86") (name "unconnected-(U3-GPIO.1{slash}RXT-Pad18)") (class "Default")
      (node (ref "U3") (pin "18") (pinfunction "GPIO.1/RXT_18") (pintype "bidirectional"))
    )
    (net (code "87") (name "unconnected-(U3-GPIO.2{slash}RS485-Pad17)") (class "Default")
      (node (ref "U3") (pin "17") (pinfunction "GPIO.2/RS485_17") (pintype "bidirectional"))
    )
    (net (code "88") (name "unconnected-(U3-GPIO.3{slash}WAKEUP-Pad16)") (class "Default")
      (node (ref "U3") (pin "16") (pinfunction "GPIO.3/WAKEUP_16") (pintype "bidirectional"))
    )
    (net (code "89") (name "unconnected-(U3-GPIO.4-Pad22)") (class "Default")
      (node (ref "U3") (pin "22") (pinfunction "GPIO.4_22") (pintype "bidirectional"))
    )
    (net (code "90") (name "unconnected-(U3-GPIO.5-Pad21)") (class "Default")
      (node (ref "U3") (pin "21") (pinfunction "GPIO.5_21") (pintype "bidirectional"))
    )
    (net (code "91") (name "unconnected-(U3-GPIO.6-Pad20)") (class "Default")
      (node (ref "U3") (pin "20") (pinfunction "GPIO.6_20") (pintype "bidirectional"))
    )
    (net (code "92") (name "unconnected-(U3-RI{slash}CLK-Pad2)") (class "Default")
      (node (ref "U3") (pin "2") (pinfunction "RI/CLK_2") (pintype "bidirectional"))
    )
    (net (code "93") (name "unconnected-(U3-SUSPEND-Pad12)") (class "Default")
      (node (ref "U3") (pin "12") (pinfunction "SUSPEND_12") (pintype "output"))
    )
    (net (code "94") (name "unconnected-(U3-~{SUSPENDB}-Pad11)") (class "Default")
      (node (ref "U3") (pin "11") (pinfunction "~{SUSPENDB}_11") (pintype "output"))
    )
  )
)
